# Page_I_B2B_B.net
KiCad netlist of a schematic drawn in Altium Designer
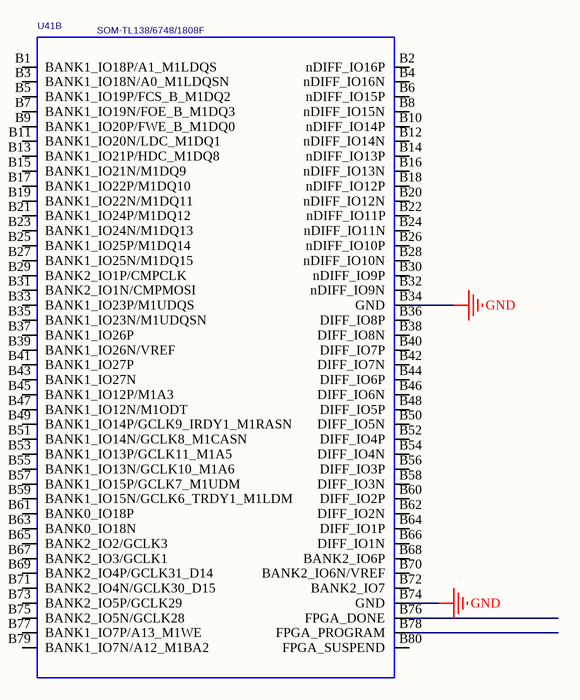
[diagram p0: Page I_B2B_B.SchDoc]

(export (version "E")
  (design (tool "Eeschema 10.0.6"))
  (components
    (comp (ref "U41")
      (value "SOM-TL138/6748/1808F")
      (footprint "TL138_6748_1808F")
      (fields (field (name "MANUFACTURER") "TL"))
      (libsource (lib "*") (part "TL_4"))
    )
  )
  (nets
    (net (code "1") (name "GND") (class "Default")
      (node (ref "U41") (pin "B34") (pinfunction "GND_B34") (pintype "power_in"))
      (node (ref "U41") (pin "B74") (pinfunction "GND_B74") (pintype "power_in"))
    )
    (net (code "2") (name "unconnected-(U41B-BANK0_IO18N-PadB63)") (class "Default")
      (node (ref "U41") (pin "B63") (pinfunction "BANK0_IO18N_B63") (pintype "passive"))
    )
    (net (code "3") (name "unconnected-(U41B-BANK0_IO18P-PadB61)") (class "Default")
      (node (ref "U41") (pin "B61") (pinfunction "BANK0_IO18P_B61") (pintype "passive"))
    )
    (net (code "4") (name "unconnected-(U41B-BANK1_IO7N{slash}A12_M1BA2-PadB79)") (class "Default")
      (node (ref "U41") (pin "B79") (pinfunction "BANK1_IO7N/A12_M1BA2_B79") (pintype "passive"))
    )
    (net (code "5") (name "unconnected-(U41B-BANK1_IO7P{slash}A13_M1WE-PadB77)") (class "Default")
      (node (ref "U41") (pin "B77") (pinfunction "BANK1_IO7P/A13_M1WE_B77") (pintype "passive"))
    )
    (net (code "6") (name "unconnected-(U41B-BANK1_IO12N{slash}M1ODT-PadB47)") (class "Default")
      (node (ref "U41") (pin "B47") (pinfunction "BANK1_IO12N/M1ODT_B47") (pintype "passive"))
    )
    (net (code "7") (name "unconnected-(U41B-BANK1_IO12P{slash}M1A3-PadB45)") (class "Default")
      (node (ref "U41") (pin "B45") (pinfunction "BANK1_IO12P/M1A3_B45") (pintype "passive"))
    )
    (net (code "8") (name "unconnected-(U41B-BANK1_IO13N{slash}GCLK10_M1A6-PadB55)") (class "Default")
      (node (ref "U41") (pin "B55") (pinfunction "BANK1_IO13N/GCLK10_M1A6_B55") (pintype "passive"))
    )
    (net (code "9") (name "unconnected-(U41B-BANK1_IO13P{slash}GCLK11_M1A5-PadB53)") (class "Default")
      (node (ref "U41") (pin "B53") (pinfunction "BANK1_IO13P/GCLK11_M1A5_B53") (pintype "passive"))
    )
    (net (code "10") (name "unconnected-(U41B-BANK1_IO14N{slash}GCLK8_M1CASN-PadB51)") (class "Default")
      (node (ref "U41") (pin "B51") (pinfunction "BANK1_IO14N/GCLK8_M1CASN_B51") (pintype "passive"))
    )
    (net (code "11") (name "unconnected-(U41B-BANK1_IO14P{slash}GCLK9_IRDY1_M1RASN-PadB49)") (class "Default")
      (node (ref "U41") (pin "B49") (pinfunction "BANK1_IO14P/GCLK9_IRDY1_M1RASN_B49") (pintype "passive"))
    )
    (net (code "12") (name "unconnected-(U41B-BANK1_IO15N{slash}GCLK6_TRDY1_M1LDM-PadB59)") (class "Default")
      (node (ref "U41") (pin "B59") (pinfunction "BANK1_IO15N/GCLK6_TRDY1_M1LDM_B59") (pintype "passive"))
    )
    (net (code "13") (name "unconnected-(U41B-BANK1_IO15P{slash}GCLK7_M1UDM-PadB57)") (class "Default")
      (node (ref "U41") (pin "B57") (pinfunction "BANK1_IO15P/GCLK7_M1UDM_B57") (pintype "passive"))
    )
    (net (code "14") (name "unconnected-(U41B-BANK1_IO18N{slash}A0_M1LDQSN-PadB3)") (class "Default")
      (node (ref "U41") (pin "B3") (pinfunction "BANK1_IO18N/A0_M1LDQSN_B3") (pintype "passive"))
    )
    (net (code "15") (name "unconnected-(U41B-BANK1_IO18P{slash}A1_M1LDQS-PadB1)") (class "Default")
      (node (ref "U41") (pin "B1") (pinfunction "BANK1_IO18P/A1_M1LDQS_B1") (pintype "passive"))
    )
    (net (code "16") (name "unconnected-(U41B-BANK1_IO19N{slash}FOE_B_M1DQ3-PadB7)") (class "Default")
      (node (ref "U41") (pin "B7") (pinfunction "BANK1_IO19N/FOE_B_M1DQ3_B7") (pintype "passive"))
    )
    (net (code "17") (name "unconnected-(U41B-BANK1_IO19P{slash}FCS_B_M1DQ2-PadB5)") (class "Default")
      (node (ref "U41") (pin "B5") (pinfunction "BANK1_IO19P/FCS_B_M1DQ2_B5") (pintype "passive"))
    )
    (net (code "18") (name "unconnected-(U41B-BANK1_IO20N{slash}LDC_M1DQ1-PadB11)") (class "Default")
      (node (ref "U41") (pin "B11") (pinfunction "BANK1_IO20N/LDC_M1DQ1_B11") (pintype "passive"))
    )
    (net (code "19") (name "unconnected-(U41B-BANK1_IO20P{slash}FWE_B_M1DQ0-PadB9)") (class "Default")
      (node (ref "U41") (pin "B9") (pinfunction "BANK1_IO20P/FWE_B_M1DQ0_B9") (pintype "passive"))
    )
    (net (code "20") (name "unconnected-(U41B-BANK1_IO21N{slash}M1DQ9-PadB15)") (class "Default")
      (node (ref "U41") (pin "B15") (pinfunction "BANK1_IO21N/M1DQ9_B15") (pintype "passive"))
    )
    (net (code "21") (name "unconnected-(U41B-BANK1_IO21P{slash}HDC_M1DQ8-PadB13)") (class "Default")
      (node (ref "U41") (pin "B13") (pinfunction "BANK1_IO21P/HDC_M1DQ8_B13") (pintype "passive"))
    )
    (net (code "22") (name "unconnected-(U41B-BANK1_IO22N{slash}M1DQ11-PadB19)") (class "Default")
      (node (ref "U41") (pin "B19") (pinfunction "BANK1_IO22N/M1DQ11_B19") (pintype "passive"))
    )
    (net (code "23") (name "unconnected-(U41B-BANK1_IO22P{slash}M1DQ10-PadB17)") (class "Default")
      (node (ref "U41") (pin "B17") (pinfunction "BANK1_IO22P/M1DQ10_B17") (pintype "passive"))
    )
    (net (code "24") (name "unconnected-(U41B-BANK1_IO23N{slash}M1UDQSN-PadB35)") (class "Default")
      (node (ref "U41") (pin "B35") (pinfunction "BANK1_IO23N/M1UDQSN_B35") (pintype "passive"))
    )
    (net (code "25") (name "unconnected-(U41B-BANK1_IO23P{slash}M1UDQS-PadB33)") (class "Default")
      (node (ref "U41") (pin "B33") (pinfunction "BANK1_IO23P/M1UDQS_B33") (pintype "passive"))
    )
    (net (code "26") (name "unconnected-(U41B-BANK1_IO24N{slash}M1DQ13-PadB23)") (class "Default")
      (node (ref "U41") (pin "B23") (pinfunction "BANK1_IO24N/M1DQ13_B23") (pintype "passive"))
    )
    (net (code "27") (name "unconnected-(U41B-BANK1_IO24P{slash}M1DQ12-PadB21)") (class "Default")
      (node (ref "U41") (pin "B21") (pinfunction "BANK1_IO24P/M1DQ12_B21") (pintype "passive"))
    )
    (net (code "28") (name "unconnected-(U41B-BANK1_IO25N{slash}M1DQ15-PadB27)") (class "Default")
      (node (ref "U41") (pin "B27") (pinfunction "BANK1_IO25N/M1DQ15_B27") (pintype "passive"))
    )
    (net (code "29") (name "unconnected-(U41B-BANK1_IO25P{slash}M1DQ14-PadB25)") (class "Default")
      (node (ref "U41") (pin "B25") (pinfunction "BANK1_IO25P/M1DQ14_B25") (pintype "passive"))
    )
    (net (code "30") (name "unconnected-(U41B-BANK1_IO26N{slash}VREF-PadB39)") (class "Default")
      (node (ref "U41") (pin "B39") (pinfunction "BANK1_IO26N/VREF_B39") (pintype "passive"))
    )
    (net (code "31") (name "unconnected-(U41B-BANK1_IO26P-PadB37)") (class "Default")
      (node (ref "U41") (pin "B37") (pinfunction "BANK1_IO26P_B37") (pintype "passive"))
    )
    (net (code "32") (name "unconnected-(U41B-BANK1_IO27N-PadB43)") (class "Default")
      (node (ref "U41") (pin "B43") (pinfunction "BANK1_IO27N_B43") (pintype "passive"))
    )
    (net (code "33") (name "unconnected-(U41B-BANK1_IO27P-PadB41)") (class "Default")
      (node (ref "U41") (pin "B41") (pinfunction "BANK1_IO27P_B41") (pintype "passive"))
    )
    (net (code "34") (name "unconnected-(U41B-BANK2_IO1N{slash}CMPMOSI-PadB31)") (class "Default")
      (node (ref "U41") (pin "B31") (pinfunction "BANK2_IO1N/CMPMOSI_B31") (pintype "passive"))
    )
    (net (code "35") (name "unconnected-(U41B-BANK2_IO1P{slash}CMPCLK-PadB29)") (class "Default")
      (node (ref "U41") (pin "B29") (pinfunction "BANK2_IO1P/CMPCLK_B29") (pintype "passive"))
    )
    (net (code "36") (name "unconnected-(U41B-BANK2_IO2{slash}GCLK3-PadB65)") (class "Default")
      (node (ref "U41") (pin "B65") (pinfunction "BANK2_IO2/GCLK3_B65") (pintype "passive"))
    )
    (net (code "37") (name "unconnected-(U41B-BANK2_IO3{slash}GCLK1-PadB67)") (class "Default")
      (node (ref "U41") (pin "B67") (pinfunction "BANK2_IO3/GCLK1_B67") (pintype "passive"))
    )
    (net (code "38") (name "unconnected-(U41B-BANK2_IO4N{slash}GCLK30_D15-PadB71)") (class "Default")
      (node (ref "U41") (pin "B71") (pinfunction "BANK2_IO4N/GCLK30_D15_B71") (pintype "passive"))
    )
    (net (code "39") (name "unconnected-(U41B-BANK2_IO4P{slash}GCLK31_D14-PadB69)") (class "Default")
      (node (ref "U41") (pin "B69") (pinfunction "BANK2_IO4P/GCLK31_D14_B69") (pintype "passive"))
    )
    (net (code "40") (name "unconnected-(U41B-BANK2_IO5N{slash}GCLK28-PadB75)") (class "Default")
      (node (ref "U41") (pin "B75") (pinfunction "BANK2_IO5N/GCLK28_B75") (pintype "passive"))
    )
    (net (code "41") (name "unconnected-(U41B-BANK2_IO5P{slash}GCLK29-PadB73)") (class "Default")
      (node (ref "U41") (pin "B73") (pinfunction "BANK2_IO5P/GCLK29_B73") (pintype "passive"))
    )
    (net (code "42") (name "unconnected-(U41B-BANK2_IO6N{slash}VREF-PadB70)") (class "Default")
      (node (ref "U41") (pin "B70") (pinfunction "BANK2_IO6N/VREF_B70") (pintype "passive"))
    )
    (net (code "43") (name "unconnected-(U41B-BANK2_IO6P-PadB68)") (class "Default")
      (node (ref "U41") (pin "B68") (pinfunction "BANK2_IO6P_B68") (pintype "passive"))
    )
    (net (code "44") (name "unconnected-(U41B-BANK2_IO7-PadB72)") (class "Default")
      (node (ref "U41") (pin "B72") (pinfunction "BANK2_IO7_B72") (pintype "passive"))
    )
    (net (code "45") (name "unconnected-(U41B-DIFF_IO1N-PadB66)") (class "Default")
      (node (ref "U41") (pin "B66") (pinfunction "DIFF_IO1N_B66") (pintype "passive"))
    )
    (net (code "46") (name "unconnected-(U41B-DIFF_IO1P-PadB64)") (class "Default")
      (node (ref "U41") (pin "B64") (pinfunction "DIFF_IO1P_B64") (pintype "passive"))
    )
    (net (code "47") (name "unconnected-(U41B-DIFF_IO2N-PadB62)") (class "Default")
      (node (ref "U41") (pin "B62") (pinfunction "DIFF_IO2N_B62") (pintype "passive"))
    )
    (net (code "48") (name "unconnected-(U41B-DIFF_IO2P-PadB60)") (class "Default")
      (node (ref "U41") (pin "B60") (pinfunction "DIFF_IO2P_B60") (pintype "passive"))
    )
    (net (code "49") (name "unconnected-(U41B-DIFF_IO3N-PadB58)") (class "Default")
      (node (ref "U41") (pin "B58") (pinfunction "DIFF_IO3N_B58") (pintype "passive"))
    )
    (net (code "50") (name "unconnected-(U41B-DIFF_IO3P-PadB56)") (class "Default")
      (node (ref "U41") (pin "B56") (pinfunction "DIFF_IO3P_B56") (pintype "passive"))
    )
    (net (code "51") (name "unconnected-(U41B-DIFF_IO4N-PadB54)") (class "Default")
      (node (ref "U41") (pin "B54") (pinfunction "DIFF_IO4N_B54") (pintype "passive"))
    )
    (net (code "52") (name "unconnected-(U41B-DIFF_IO4P-PadB52)") (class "Default")
      (node (ref "U41") (pin "B52") (pinfunction "DIFF_IO4P_B52") (pintype "passive"))
    )
    (net (code "53") (name "unconnected-(U41B-DIFF_IO5N-PadB50)") (class "Default")
      (node (ref "U41") (pin "B50") (pinfunction "DIFF_IO5N_B50") (pintype "passive"))
    )
    (net (code "54") (name "unconnected-(U41B-DIFF_IO5P-PadB48)") (class "Default")
      (node (ref "U41") (pin "B48") (pinfunction "DIFF_IO5P_B48") (pintype "passive"))
    )
    (net (code "55") (name "unconnected-(U41B-DIFF_IO6N-PadB46)") (class "Default")
      (node (ref "U41") (pin "B46") (pinfunction "DIFF_IO6N_B46") (pintype "passive"))
    )
    (net (code "56") (name "unconnected-(U41B-DIFF_IO6P-PadB44)") (class "Default")
      (node (ref "U41") (pin "B44") (pinfunction "DIFF_IO6P_B44") (pintype "passive"))
    )
    (net (code "57") (name "unconnected-(U41B-DIFF_IO7N-PadB42)") (class "Default")
      (node (ref "U41") (pin "B42") (pinfunction "DIFF_IO7N_B42") (pintype "passive"))
    )
    (net (code "58") (name "unconnected-(U41B-DIFF_IO7P-PadB40)") (class "Default")
      (node (ref "U41") (pin "B40") (pinfunction "DIFF_IO7P_B40") (pintype "passive"))
    )
    (net (code "59") (name "unconnected-(U41B-DIFF_IO8N-PadB38)") (class "Default")
      (node (ref "U41") (pin "B38") (pinfunction "DIFF_IO8N_B38") (pintype "passive"))
    )
    (net (code "60") (name "unconnected-(U41B-DIFF_IO8P-PadB36)") (class "Default")
      (node (ref "U41") (pin "B36") (pinfunction "DIFF_IO8P_B36") (pintype "passive"))
    )
    (net (code "61") (name "unconnected-(U41B-FPGA_DONE-PadB76)") (class "Default")
      (node (ref "U41") (pin "B76") (pinfunction "FPGA_DONE_B76") (pintype "passive"))
    )
    (net (code "62") (name "unconnected-(U41B-FPGA_PROGRAM-PadB78)") (class "Default")
      (node (ref "U41") (pin "B78") (pinfunction "FPGA_PROGRAM_B78") (pintype "passive"))
    )
    (net (code "63") (name "unconnected-(U41B-FPGA_SUSPEND-PadB80)") (class "Default")
      (node (ref "U41") (pin "B80") (pinfunction "FPGA_SUSPEND_B80") (pintype "passive"))
    )
    (net (code "64") (name "unconnected-(U41B-nDIFF_IO9N-PadB32)") (class "Default")
      (node (ref "U41") (pin "B32") (pinfunction "nDIFF_IO9N_B32") (pintype "passive"))
    )
    (net (code "65") (name "unconnected-(U41B-nDIFF_IO9P-PadB30)") (class "Default")
      (node (ref "U41") (pin "B30") (pinfunction "nDIFF_IO9P_B30") (pintype "passive"))
    )
    (net (code "66") (name "unconnected-(U41B-nDIFF_IO10N-PadB28)") (class "Default")
      (node (ref "U41") (pin "B28") (pinfunction "nDIFF_IO10N_B28") (pintype "passive"))
    )
    (net (code "67") (name "unconnected-(U41B-nDIFF_IO10P-PadB26)") (class "Default")
      (node (ref "U41") (pin "B26") (pinfunction "nDIFF_IO10P_B26") (pintype "passive"))
    )
    (net (code "68") (name "unconnected-(U41B-nDIFF_IO11N-PadB24)") (class "Default")
      (node (ref "U41") (pin "B24") (pinfunction "nDIFF_IO11N_B24") (pintype "passive"))
    )
    (net (code "69") (name "unconnected-(U41B-nDIFF_IO11P-PadB22)") (class "Default")
      (node (ref "U41") (pin "B22") (pinfunction "nDIFF_IO11P_B22") (pintype "passive"))
    )
    (net (code "70") (name "unconnected-(U41B-nDIFF_IO12N-PadB20)") (class "Default")
      (node (ref "U41") (pin "B20") (pinfunction "nDIFF_IO12N_B20") (pintype "passive"))
    )
    (net (code "71") (name "unconnected-(U41B-nDIFF_IO12P-PadB18)") (class "Default")
      (node (ref "U41") (pin "B18") (pinfunction "nDIFF_IO12P_B18") (pintype "passive"))
    )
    (net (code "72") (name "unconnected-(U41B-nDIFF_IO13N-PadB16)") (class "Default")
      (node (ref "U41") (pin "B16") (pinfunction "nDIFF_IO13N_B16") (pintype "passive"))
    )
    (net (code "73") (name "unconnected-(U41B-nDIFF_IO13P-PadB14)") (class "Default")
      (node (ref "U41") (pin "B14") (pinfunction "nDIFF_IO13P_B14") (pintype "passive"))
    )
    (net (code "74") (name "unconnected-(U41B-nDIFF_IO14N-PadB12)") (class "Default")
      (node (ref "U41") (pin "B12") (pinfunction "nDIFF_IO14N_B12") (pintype "passive"))
    )
    (net (code "75") (name "unconnected-(U41B-nDIFF_IO14P-PadB10)") (class "Default")
      (node (ref "U41") (pin "B10") (pinfunction "nDIFF_IO14P_B10") (pintype "passive"))
    )
    (net (code "76") (name "unconnected-(U41B-nDIFF_IO15N-PadB8)") (class "Default")
      (node (ref "U41") (pin "B8") (pinfunction "nDIFF_IO15N_B8") (pintype "passive"))
    )
    (net (code "77") (name "unconnected-(U41B-nDIFF_IO15P-PadB6)") (class "Default")
      (node (ref "U41") (pin "B6") (pinfunction "nDIFF_IO15P_B6") (pintype "passive"))
    )
    (net (code "78") (name "unconnected-(U41B-nDIFF_IO16N-PadB4)") (class "Default")
      (node (ref "U41") (pin "B4") (pinfunction "nDIFF_IO16N_B4") (pintype "passive"))
    )
    (net (code "79") (name "unconnected-(U41B-nDIFF_IO16P-PadB2)") (class "Default")
      (node (ref "U41") (pin "B2") (pinfunction "nDIFF_IO16P_B2") (pintype "passive"))
    )
  )
)
